# clogic.net
KiCad netlist of a schematic drawn in EAGLE
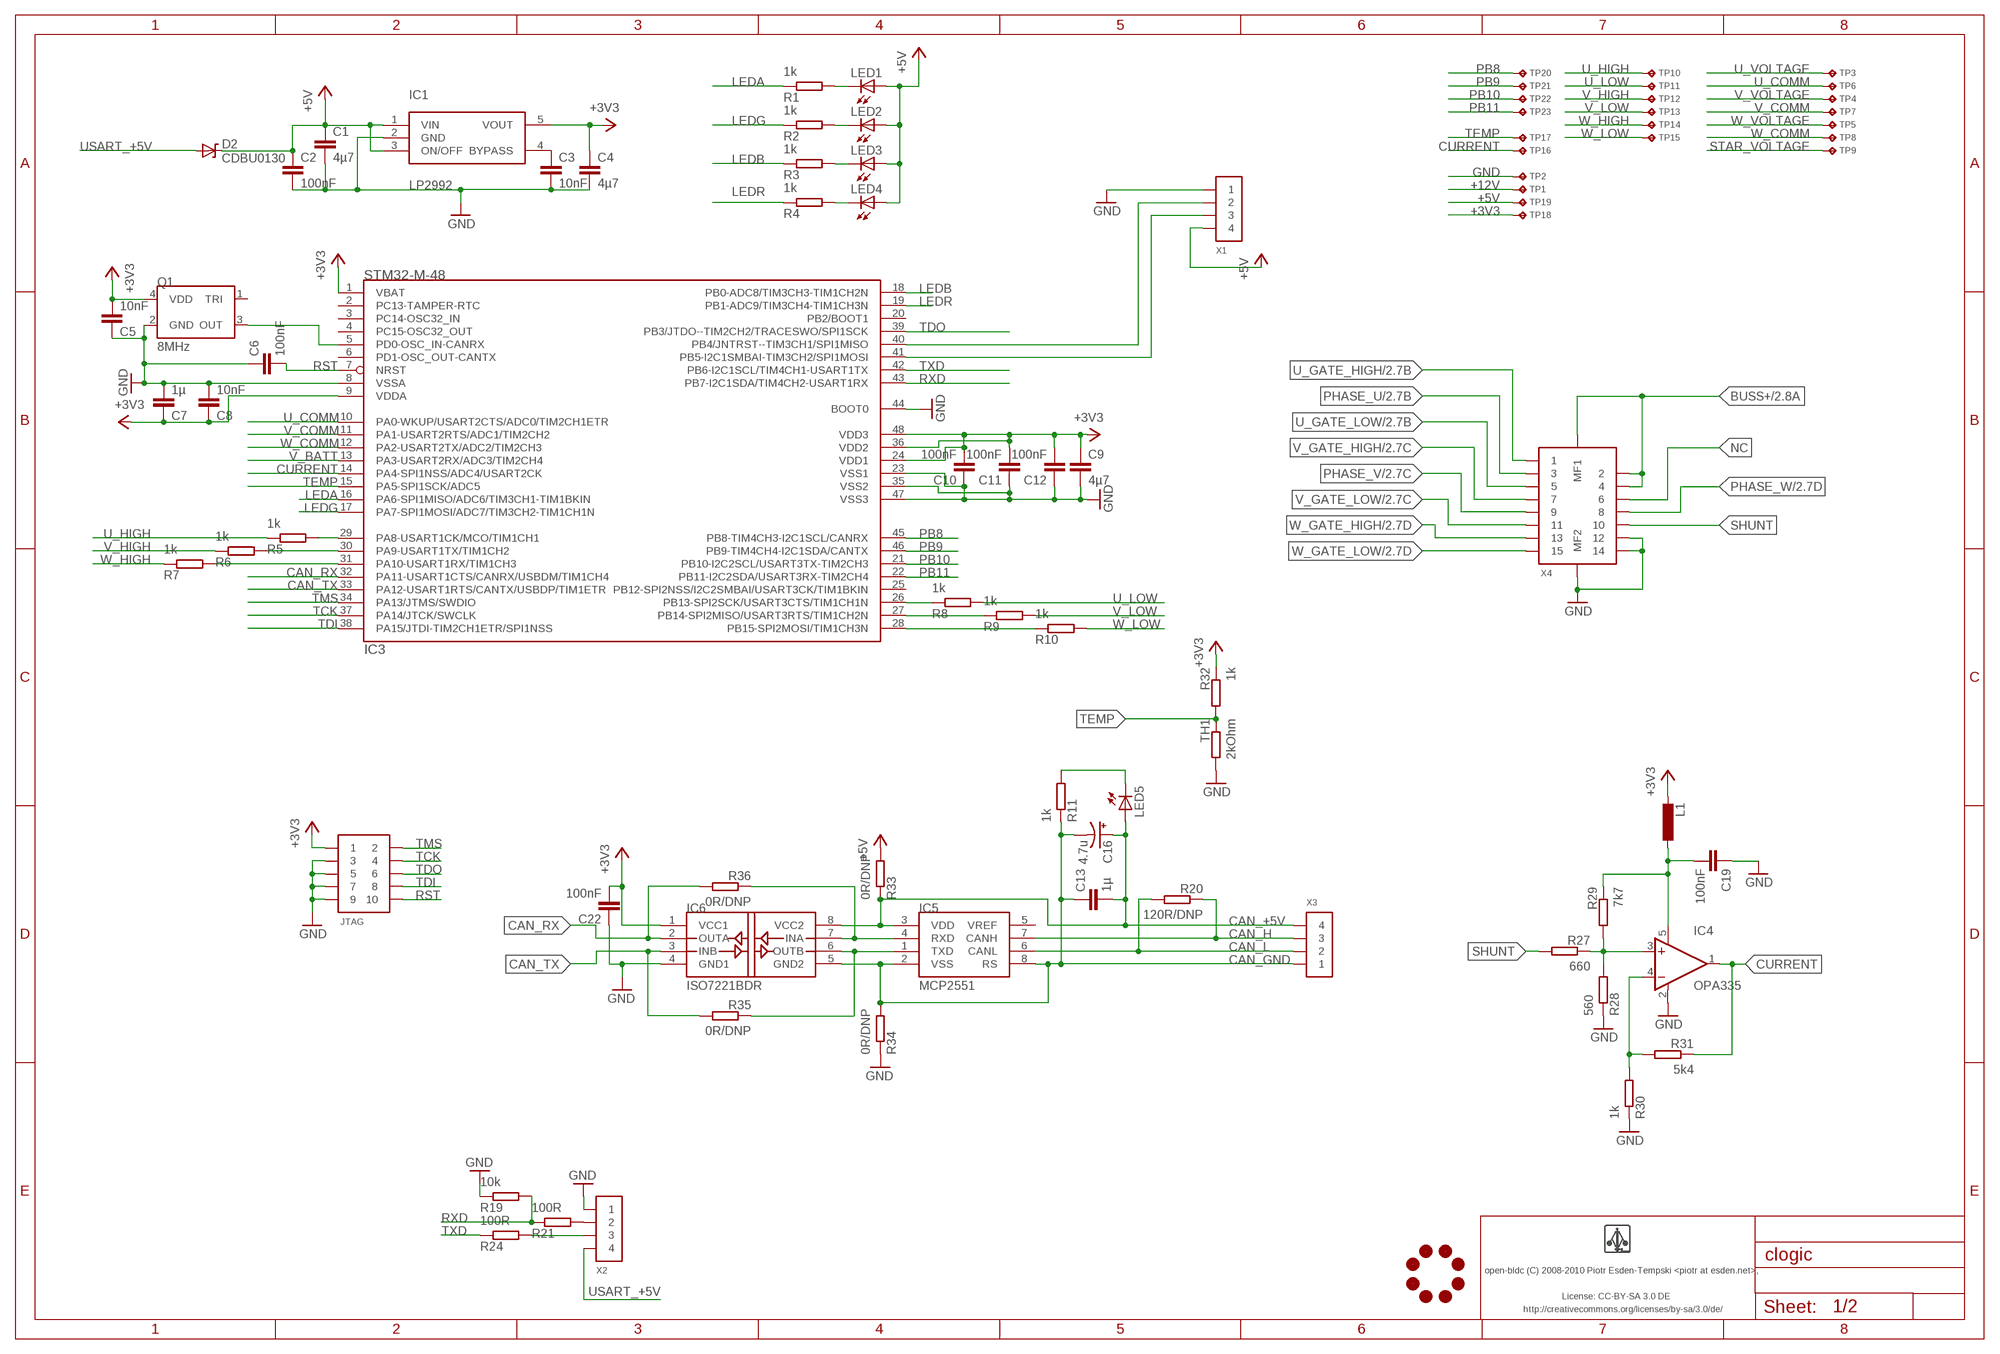
[diagram p0: schematic, sheet 1]
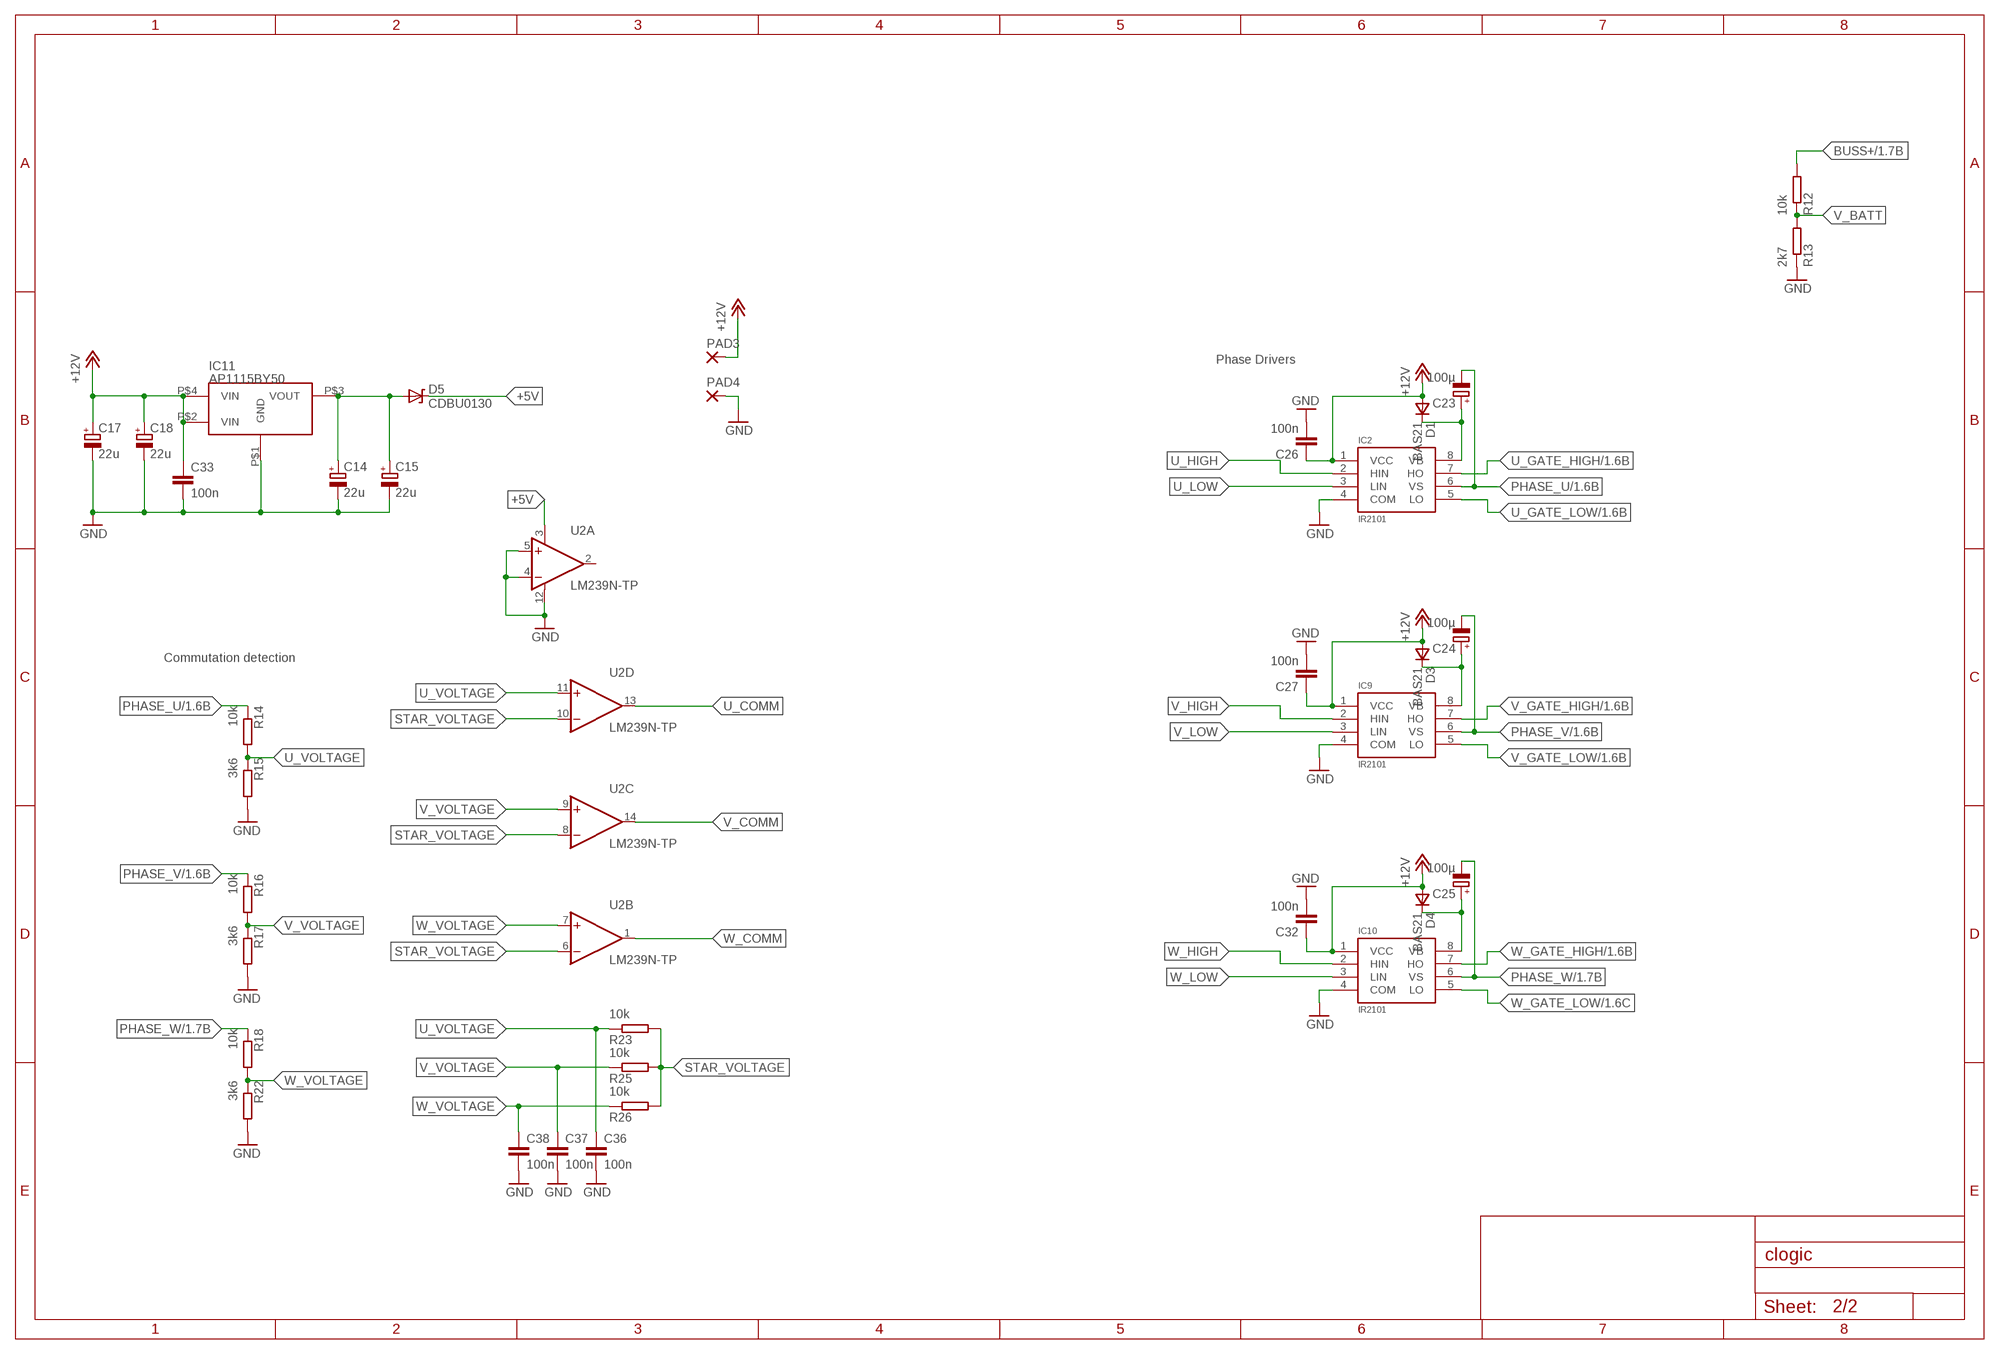
[diagram p1: schematic, sheet 2]

(export (version "E")
  (design (tool "Eeschema 10.0.6"))
  (components
    (comp (ref "C14")
      (value "22u")
      (footprint "eagle-import:0805-POL-CAP")
      (libsource (lib "eagle-import") (part "CAPACITOR-POL-0805"))
    )
    (comp (ref "C15")
      (value "22u")
      (footprint "eagle-import:0805-POL-CAP")
      (libsource (lib "eagle-import") (part "CAPACITOR-POL-0805"))
    )
    (comp (ref "C17")
      (value "22u")
      (footprint "eagle-import:0805-POL-CAP")
      (libsource (lib "eagle-import") (part "CAPACITOR-POL-0805"))
    )
    (comp (ref "C18")
      (value "22u")
      (footprint "eagle-import:0805-POL-CAP")
      (libsource (lib "eagle-import") (part "CAPACITOR-POL-0805"))
    )
    (comp (ref "C23")
      (value "100µ")
      (footprint "eagle-import:0805-POL-CAP")
      (libsource (lib "eagle-import") (part "CAPACITOR-POL-0805"))
    )
    (comp (ref "C24")
      (value "100µ")
      (footprint "eagle-import:0805-POL-CAP")
      (libsource (lib "eagle-import") (part "CAPACITOR-POL-0805"))
    )
    (comp (ref "C25")
      (value "100µ")
      (footprint "eagle-import:0805-POL-CAP")
      (libsource (lib "eagle-import") (part "CAPACITOR-POL-0805"))
    )
    (comp (ref "C26")
      (value "100n")
      (footprint "eagle-import:0603-CAP")
      (libsource (lib "eagle-import") (part "CAPACITOR-0603"))
    )
    (comp (ref "C27")
      (value "100n")
      (footprint "eagle-import:0603-CAP")
      (libsource (lib "eagle-import") (part "CAPACITOR-0603"))
    )
    (comp (ref "C32")
      (value "100n")
      (footprint "eagle-import:0603-CAP")
      (libsource (lib "eagle-import") (part "CAPACITOR-0603"))
    )
    (comp (ref "C33")
      (value "100n")
      (footprint "eagle-import:0603-CAP")
      (libsource (lib "eagle-import") (part "CAPACITOR-0603"))
    )
    (comp (ref "C36")
      (value "100n")
      (footprint "eagle-import:0603-CAP")
      (libsource (lib "eagle-import") (part "CAPACITOR-0603"))
    )
    (comp (ref "C37")
      (value "100n")
      (footprint "eagle-import:0603-CAP")
      (libsource (lib "eagle-import") (part "CAPACITOR-0603"))
    )
    (comp (ref "C38")
      (value "100n")
      (footprint "eagle-import:0603-CAP")
      (libsource (lib "eagle-import") (part "CAPACITOR-0603"))
    )
    (comp (ref "D1")
      (value "BAS21")
      (footprint "eagle-import:SOT-23")
      (libsource (lib "eagle-import") (part "VAR2SOT23"))
    )
    (comp (ref "D3")
      (value "BAS21")
      (footprint "eagle-import:SOT-23")
      (libsource (lib "eagle-import") (part "VAR2SOT23"))
    )
    (comp (ref "D4")
      (value "BAS21")
      (footprint "eagle-import:SOT-23")
      (libsource (lib "eagle-import") (part "VAR2SOT23"))
    )
    (comp (ref "D5")
      (value "CDBU0130")
      (footprint "eagle-import:0603-LED")
      (libsource (lib "eagle-import") (part "DIODE-ZENER-0603"))
    )
    (comp (ref "IC2")
      (value "IR2101")
      (footprint "eagle-import:SO-8")
      (libsource (lib "eagle-import") (part "IR2101"))
    )
    (comp (ref "IC9")
      (value "IR2101")
      (footprint "eagle-import:SO-8")
      (libsource (lib "eagle-import") (part "IR2101"))
    )
    (comp (ref "IC10")
      (value "IR2101")
      (footprint "eagle-import:SO-8")
      (libsource (lib "eagle-import") (part "IR2101"))
    )
    (comp (ref "IC11")
      (value "AP1115BY50")
      (footprint "eagle-import:SOT89")
      (libsource (lib "eagle-import") (part "AP1115BY50"))
    )
    (comp (ref "PAD3")
      (value "SMD5")
      (footprint "eagle-import:SMD2,54-5,08")
      (libsource (lib "eagle-import") (part "SMD5"))
    )
    (comp (ref "PAD4")
      (value "SMD5")
      (footprint "eagle-import:SMD2,54-5,08")
      (libsource (lib "eagle-import") (part "SMD5"))
    )
    (comp (ref "R12")
      (value "10k")
      (footprint "eagle-import:0603-RES")
      (libsource (lib "eagle-import") (part "RESISTOR-0603"))
    )
    (comp (ref "R13")
      (value "2k7")
      (footprint "eagle-import:0603-RES")
      (libsource (lib "eagle-import") (part "RESISTOR-0603"))
    )
    (comp (ref "R14")
      (value "10k")
      (footprint "eagle-import:0603-RES")
      (libsource (lib "eagle-import") (part "RESISTOR-0603"))
    )
    (comp (ref "R15")
      (value "3k6")
      (footprint "eagle-import:0603-RES")
      (libsource (lib "eagle-import") (part "RESISTOR-0603"))
    )
    (comp (ref "R16")
      (value "10k")
      (footprint "eagle-import:0603-RES")
      (libsource (lib "eagle-import") (part "RESISTOR-0603"))
    )
    (comp (ref "R17")
      (value "3k6")
      (footprint "eagle-import:0603-RES")
      (libsource (lib "eagle-import") (part "RESISTOR-0603"))
    )
    (comp (ref "R18")
      (value "10k")
      (footprint "eagle-import:0603-RES")
      (libsource (lib "eagle-import") (part "RESISTOR-0603"))
    )
    (comp (ref "R22")
      (value "3k6")
      (footprint "eagle-import:0603-RES")
      (libsource (lib "eagle-import") (part "RESISTOR-0603"))
    )
    (comp (ref "R23")
      (value "10k")
      (footprint "eagle-import:0603-RES")
      (libsource (lib "eagle-import") (part "RESISTOR-0603"))
    )
    (comp (ref "R25")
      (value "10k")
      (footprint "eagle-import:0603-RES")
      (libsource (lib "eagle-import") (part "RESISTOR-0603"))
    )
    (comp (ref "R26")
      (value "10k")
      (footprint "eagle-import:0603-RES")
      (libsource (lib "eagle-import") (part "RESISTOR-0603"))
    )
    (comp (ref "U2")
      (value "LM239N-TP")
      (footprint "eagle-import:TSSOP_14")
      (libsource (lib "eagle-import") (part "LM239N-TP"))
    )
    (comp (ref "C1")
      (value "4µ7")
      (footprint "eagle-import:0603-CAP")
      (libsource (lib "eagle-import") (part "CAPACITOR-0603"))
    )
    (comp (ref "C2")
      (value "100nF")
      (footprint "eagle-import:0603-CAP")
      (libsource (lib "eagle-import") (part "CAPACITOR-0603"))
    )
    (comp (ref "C3")
      (value "10nF")
      (footprint "eagle-import:0603-CAP")
      (libsource (lib "eagle-import") (part "CAPACITOR-0603"))
    )
    (comp (ref "C4")
      (value "4µ7")
      (footprint "eagle-import:0603-CAP")
      (libsource (lib "eagle-import") (part "CAPACITOR-0603"))
    )
    (comp (ref "C5")
      (value "10nF")
      (footprint "eagle-import:0603-CAP")
      (libsource (lib "eagle-import") (part "CAPACITOR-0603"))
    )
    (comp (ref "C6")
      (value "100nF")
      (footprint "eagle-import:0603-CAP")
      (libsource (lib "eagle-import") (part "CAPACITOR-0603"))
    )
    (comp (ref "C7")
      (value "1µ")
      (footprint "eagle-import:0603-CAP")
      (libsource (lib "eagle-import") (part "CAPACITOR-0603"))
    )
    (comp (ref "C8")
      (value "10nF")
      (footprint "eagle-import:0603-CAP")
      (libsource (lib "eagle-import") (part "CAPACITOR-0603"))
    )
    (comp (ref "C9")
      (value "4µ7")
      (footprint "eagle-import:0603-CAP")
      (libsource (lib "eagle-import") (part "CAPACITOR-0603"))
    )
    (comp (ref "C10")
      (value "100nF")
      (footprint "eagle-import:0603-CAP")
      (libsource (lib "eagle-import") (part "CAPACITOR-0603"))
    )
    (comp (ref "C11")
      (value "100nF")
      (footprint "eagle-import:0603-CAP")
      (libsource (lib "eagle-import") (part "CAPACITOR-0603"))
    )
    (comp (ref "C12")
      (value "100nF")
      (footprint "eagle-import:0603-CAP")
      (libsource (lib "eagle-import") (part "CAPACITOR-0603"))
    )
    (comp (ref "C13")
      (value "1µ")
      (footprint "eagle-import:0603-CAP")
      (libsource (lib "eagle-import") (part "CAPACITOR-0603"))
    )
    (comp (ref "C16")
      (value "4.7u")
      (footprint "eagle-import:CAP_0805TANT_F95")
      (libsource (lib "eagle-import") (part "CPOL-US"))
    )
    (comp (ref "C19")
      (value "100nF")
      (footprint "eagle-import:0603-CAP")
      (libsource (lib "eagle-import") (part "CAPACITOR-0603"))
    )
    (comp (ref "C22")
      (value "100nF")
      (footprint "eagle-import:0603-CAP")
      (libsource (lib "eagle-import") (part "CAPACITOR-0603"))
    )
    (comp (ref "D2")
      (value "CDBU0130")
      (footprint "eagle-import:0603-LED")
      (libsource (lib "eagle-import") (part "DIODE-ZENER-0603"))
    )
    (comp (ref "IC1")
      (value "LP2992")
      (footprint "eagle-import:SOT23-5")
      (libsource (lib "eagle-import") (part "LP2992"))
    )
    (comp (ref "IC3")
      (value "STM32-M-48")
      (footprint "eagle-import:LQFP48")
      (libsource (lib "eagle-import") (part "STM32-M-48"))
    )
    (comp (ref "IC4")
      (value "OPA335")
      (footprint "eagle-import:SOT23-5")
      (libsource (lib "eagle-import") (part "OPA335"))
    )
    (comp (ref "IC5")
      (value "MCP2551")
      (footprint "eagle-import:SO8")
      (libsource (lib "eagle-import") (part "MCP2551"))
    )
    (comp (ref "IC6")
      (value "ISO7221BDR")
      (footprint "eagle-import:SO8")
      (libsource (lib "eagle-import") (part "ISO7221"))
    )
    (comp (ref "JL1")
      (value "JOBY_LOGO-6MIL")
      (footprint "eagle-import:JOBY_LOGO_6MIL")
      (libsource (lib "eagle-import") (part "JOBY_LOGO-6MIL"))
    )
    (comp (ref "JTAG")
      (value "CONN_5-2-FTSH-V")
      (footprint "eagle-import:FTSH-105-DV")
      (libsource (lib "eagle-import") (part "CONN_5-2-FTSH-V"))
    )
    (comp (ref "L1")
      (value "INDUCTOR-0603")
      (footprint "eagle-import:0603-IND")
      (libsource (lib "eagle-import") (part "INDUCTOR-0603"))
    )
    (comp (ref "LED1")
      (value "AMBER")
      (footprint "eagle-import:0603-LED")
      (libsource (lib "eagle-import") (part "LED-0603"))
    )
    (comp (ref "LED2")
      (value "GREEN")
      (footprint "eagle-import:0603-LED")
      (libsource (lib "eagle-import") (part "LED-0603"))
    )
    (comp (ref "LED3")
      (value "BLUE")
      (footprint "eagle-import:0603-LED")
      (libsource (lib "eagle-import") (part "LED-0603"))
    )
    (comp (ref "LED4")
      (value "RED")
      (footprint "eagle-import:0603-LED")
      (libsource (lib "eagle-import") (part "LED-0603"))
    )
    (comp (ref "LED5")
      (value "WHITE")
      (footprint "eagle-import:0603-LED")
      (libsource (lib "eagle-import") (part "LED-0603"))
    )
    (comp (ref "Q1")
      (value "8MHz")
      (footprint "eagle-import:ASE_OSCILLATOR")
      (libsource (lib "eagle-import") (part "ASE_ASCILLATOR"))
    )
    (comp (ref "R1")
      (value "1k")
      (footprint "eagle-import:0603-RES")
      (libsource (lib "eagle-import") (part "RESISTOR-0603"))
    )
    (comp (ref "R2")
      (value "1k")
      (footprint "eagle-import:0603-RES")
      (libsource (lib "eagle-import") (part "RESISTOR-0603"))
    )
    (comp (ref "R3")
      (value "1k")
      (footprint "eagle-import:0603-RES")
      (libsource (lib "eagle-import") (part "RESISTOR-0603"))
    )
    (comp (ref "R4")
      (value "1k")
      (footprint "eagle-import:0603-RES")
      (libsource (lib "eagle-import") (part "RESISTOR-0603"))
    )
    (comp (ref "R5")
      (value "1k")
      (footprint "eagle-import:0603-RES")
      (libsource (lib "eagle-import") (part "RESISTOR-0603"))
    )
    (comp (ref "R6")
      (value "1k")
      (footprint "eagle-import:0603-RES")
      (libsource (lib "eagle-import") (part "RESISTOR-0603"))
    )
    (comp (ref "R7")
      (value "1k")
      (footprint "eagle-import:0603-RES")
      (libsource (lib "eagle-import") (part "RESISTOR-0603"))
    )
    (comp (ref "R8")
      (value "1k")
      (footprint "eagle-import:0603-RES")
      (libsource (lib "eagle-import") (part "RESISTOR-0603"))
    )
    (comp (ref "R9")
      (value "1k")
      (footprint "eagle-import:0603-RES")
      (libsource (lib "eagle-import") (part "RESISTOR-0603"))
    )
    (comp (ref "R10")
      (value "1k")
      (footprint "eagle-import:0603-RES")
      (libsource (lib "eagle-import") (part "RESISTOR-0603"))
    )
    (comp (ref "R11")
      (value "1k")
      (footprint "eagle-import:0603-RES")
      (libsource (lib "eagle-import") (part "RESISTOR-0603"))
    )
    (comp (ref "R19")
      (value "10k")
      (footprint "eagle-import:0603-RES")
      (libsource (lib "eagle-import") (part "RESISTOR-0603"))
    )
    (comp (ref "R20")
      (value "120R/DNP")
      (footprint "eagle-import:0603-RES")
      (libsource (lib "eagle-import") (part "RESISTOR-0603"))
    )
    (comp (ref "R21")
      (value "100R")
      (footprint "eagle-import:0603-RES")
      (libsource (lib "eagle-import") (part "RESISTOR-0603"))
    )
    (comp (ref "R24")
      (value "100R")
      (footprint "eagle-import:0603-RES")
      (libsource (lib "eagle-import") (part "RESISTOR-0603"))
    )
    (comp (ref "R27")
      (value "660")
      (footprint "eagle-import:0603-RES")
      (libsource (lib "eagle-import") (part "RESISTOR-0603"))
    )
    (comp (ref "R28")
      (value "560")
      (footprint "eagle-import:0603-RES")
      (libsource (lib "eagle-import") (part "RESISTOR-0603"))
    )
    (comp (ref "R29")
      (value "7k7")
      (footprint "eagle-import:0603-RES")
      (libsource (lib "eagle-import") (part "RESISTOR-0603"))
    )
    (comp (ref "R30")
      (value "1k")
      (footprint "eagle-import:0603-RES")
      (libsource (lib "eagle-import") (part "RESISTOR-0603"))
    )
    (comp (ref "R31")
      (value "5k4")
      (footprint "eagle-import:0603-RES")
      (libsource (lib "eagle-import") (part "RESISTOR-0603"))
    )
    (comp (ref "R32")
      (value "1k")
      (footprint "eagle-import:0603-RES")
      (libsource (lib "eagle-import") (part "RESISTOR-0603"))
    )
    (comp (ref "R33")
      (value "0R/DNP")
      (footprint "eagle-import:0603-RES")
      (libsource (lib "eagle-import") (part "RESISTOR-0603"))
    )
    (comp (ref "R34")
      (value "0R/DNP")
      (footprint "eagle-import:0603-RES")
      (libsource (lib "eagle-import") (part "RESISTOR-0603"))
    )
    (comp (ref "R35")
      (value "0R/DNP")
      (footprint "eagle-import:0603-RES")
      (libsource (lib "eagle-import") (part "RESISTOR-0603"))
    )
    (comp (ref "R36")
      (value "0R/DNP")
      (footprint "eagle-import:0603-RES")
      (libsource (lib "eagle-import") (part "RESISTOR-0603"))
    )
    (comp (ref "TH1")
      (value "2kOhm")
      (footprint "eagle-import:0603-RES")
      (libsource (lib "eagle-import") (part "RESISTOR-0603"))
    )
    (comp (ref "TP1")
      (value "TP-09RSMD")
      (footprint "eagle-import:TP09R")
      (libsource (lib "eagle-import") (part "TP-09RSMD"))
    )
    (comp (ref "TP2")
      (value "TP-09RSMD")
      (footprint "eagle-import:TP09R")
      (libsource (lib "eagle-import") (part "TP-09RSMD"))
    )
    (comp (ref "TP3")
      (value "TP-09RSMD")
      (footprint "eagle-import:TP09R")
      (libsource (lib "eagle-import") (part "TP-09RSMD"))
    )
    (comp (ref "TP4")
      (value "TP-09RSMD")
      (footprint "eagle-import:TP09R")
      (libsource (lib "eagle-import") (part "TP-09RSMD"))
    )
    (comp (ref "TP5")
      (value "TP-09RSMD")
      (footprint "eagle-import:TP09R")
      (libsource (lib "eagle-import") (part "TP-09RSMD"))
    )
    (comp (ref "TP6")
      (value "TP-09RSMD")
      (footprint "eagle-import:TP09R")
      (libsource (lib "eagle-import") (part "TP-09RSMD"))
    )
    (comp (ref "TP7")
      (value "TP-09RSMD")
      (footprint "eagle-import:TP09R")
      (libsource (lib "eagle-import") (part "TP-09RSMD"))
    )
    (comp (ref "TP8")
      (value "TP-09RSMD")
      (footprint "eagle-import:TP09R")
      (libsource (lib "eagle-import") (part "TP-09RSMD"))
    )
    (comp (ref "TP9")
      (value "TP-09RSMD")
      (footprint "eagle-import:TP09R")
      (libsource (lib "eagle-import") (part "TP-09RSMD"))
    )
    (comp (ref "TP10")
      (value "TP-09RSMD")
      (footprint "eagle-import:TP09R")
      (libsource (lib "eagle-import") (part "TP-09RSMD"))
    )
    (comp (ref "TP11")
      (value "TP-09RSMD")
      (footprint "eagle-import:TP09R")
      (libsource (lib "eagle-import") (part "TP-09RSMD"))
    )
    (comp (ref "TP12")
      (value "TP-09RSMD")
      (footprint "eagle-import:TP09R")
      (libsource (lib "eagle-import") (part "TP-09RSMD"))
    )
    (comp (ref "TP13")
      (value "TP-09RSMD")
      (footprint "eagle-import:TP09R")
      (libsource (lib "eagle-import") (part "TP-09RSMD"))
    )
    (comp (ref "TP14")
      (value "TP-09RSMD")
      (footprint "eagle-import:TP09R")
      (libsource (lib "eagle-import") (part "TP-09RSMD"))
    )
    (comp (ref "TP15")
      (value "TP-09RSMD")
      (footprint "eagle-import:TP09R")
      (libsource (lib "eagle-import") (part "TP-09RSMD"))
    )
    (comp (ref "TP16")
      (value "TP-09RSMD")
      (footprint "eagle-import:TP09R")
      (libsource (lib "eagle-import") (part "TP-09RSMD"))
    )
    (comp (ref "TP17")
      (value "TP-09RSMD")
      (footprint "eagle-import:TP09R")
      (libsource (lib "eagle-import") (part "TP-09RSMD"))
    )
    (comp (ref "TP18")
      (value "TP-09RSMD")
      (footprint "eagle-import:TP09R")
      (libsource (lib "eagle-import") (part "TP-09RSMD"))
    )
    (comp (ref "TP19")
      (value "TP-09RSMD")
      (footprint "eagle-import:TP09R")
      (libsource (lib "eagle-import") (part "TP-09RSMD"))
    )
    (comp (ref "TP20")
      (value "TP-09RSMD")
      (footprint "eagle-import:TP09R")
      (libsource (lib "eagle-import") (part "TP-09RSMD"))
    )
    (comp (ref "TP21")
      (value "TP-09RSMD")
      (footprint "eagle-import:TP09R")
      (libsource (lib "eagle-import") (part "TP-09RSMD"))
    )
    (comp (ref "TP22")
      (value "TP-09RSMD")
      (footprint "eagle-import:TP09R")
      (libsource (lib "eagle-import") (part "TP-09RSMD"))
    )
    (comp (ref "TP23")
      (value "TP-09RSMD")
      (footprint "eagle-import:TP09R")
      (libsource (lib "eagle-import") (part "TP-09RSMD"))
    )
    (comp (ref "U$1")
      (value "LOGO")
      (footprint "eagle-import:LOGO")
      (libsource (lib "eagle-import") (part "LOGO-NORM"))
    )
    (comp (ref "X1")
      (value "CONN_4-1-53261")
      (footprint "eagle-import:PB-53261-04")
      (libsource (lib "eagle-import") (part "CONN_4-1-53261"))
    )
    (comp (ref "X2")
      (value "CONN_4-1-53261")
      (footprint "eagle-import:PB-53261-04")
      (libsource (lib "eagle-import") (part "CONN_4-1-53261"))
    )
    (comp (ref "X3")
      (value "CONN_4-1-53261")
      (footprint "eagle-import:PB-53261-04")
      (libsource (lib "eagle-import") (part "CONN_4-1-53261"))
    )
    (comp (ref "X4")
      (value "CONN_15-2-2MT-DF9")
      (footprint "eagle-import:DF9-15")
      (libsource (lib "eagle-import") (part "CONN_15-2-2MT-DF9"))
    )
  )
  (nets
    (net (code "1") (name "+3V3") (class "Default")
      (node (ref "C10") (pin "P$2") (pinfunction "2_P$2") (pintype "passive"))
      (node (ref "C11") (pin "P$2") (pinfunction "2_P$2") (pintype "passive"))
      (node (ref "C12") (pin "P$2") (pinfunction "2_P$2") (pintype "passive"))
      (node (ref "C22") (pin "P$2") (pinfunction "2_P$2") (pintype "passive"))
      (node (ref "C4") (pin "P$1") (pinfunction "1_P$1") (pintype "passive"))
      (node (ref "C5") (pin "P$2") (pinfunction "2_P$2") (pintype "passive"))
      (node (ref "C7") (pin "P$1") (pinfunction "1_P$1") (pintype "passive"))
      (node (ref "C8") (pin "P$1") (pinfunction "1_P$1") (pintype "passive"))
      (node (ref "C9") (pin "P$1") (pinfunction "1_P$1") (pintype "passive"))
      (node (ref "IC1") (pin "5") (pinfunction "VOUT_5") (pintype "bidirectional"))
      (node (ref "IC3") (pin "1") (pinfunction "VBAT_1") (pintype "power_in"))
      (node (ref "IC3") (pin "24") (pinfunction "VDD1_24") (pintype "power_in"))
      (node (ref "IC3") (pin "36") (pinfunction "VDD2_36") (pintype "power_in"))
      (node (ref "IC3") (pin "48") (pinfunction "VDD3_48") (pintype "power_in"))
      (node (ref "IC3") (pin "9") (pinfunction "VDDA_9") (pintype "power_in"))
      (node (ref "IC6") (pin "1") (pinfunction "VCC1_1") (pintype "bidirectional"))
      (node (ref "JTAG") (pin "1") (pinfunction "1_1") (pintype "bidirectional"))
      (node (ref "L1") (pin "P$2") (pinfunction "2_P$2") (pintype "passive"))
      (node (ref "Q1") (pin "4") (pinfunction "VDD_4") (pintype "power_in"))
      (node (ref "R32") (pin "P$1") (pinfunction "1_P$1") (pintype "passive"))
      (node (ref "TP18") (pin "P$1") (pinfunction "1_P$1") (pintype "bidirectional"))
    )
    (net (code "2") (name "+5V") (class "Default")
      (node (ref "C1") (pin "P$1") (pinfunction "1_P$1") (pintype "passive"))
      (node (ref "C2") (pin "P$1") (pinfunction "1_P$1") (pintype "passive"))
      (node (ref "D2") (pin "C") (pinfunction "C_C") (pintype "passive"))
      (node (ref "D5") (pin "C") (pinfunction "C_C") (pintype "passive"))
      (node (ref "IC1") (pin "1") (pinfunction "VIN_1") (pintype "bidirectional"))
      (node (ref "IC1") (pin "3") (pinfunction "ON/OFF_3") (pintype "bidirectional"))
      (node (ref "LED1") (pin "A") (pinfunction "A_A") (pintype "passive"))
      (node (ref "LED2") (pin "A") (pinfunction "A_A") (pintype "passive"))
      (node (ref "LED3") (pin "A") (pinfunction "A_A") (pintype "passive"))
      (node (ref "LED4") (pin "A") (pinfunction "A_A") (pintype "passive"))
      (node (ref "R33") (pin "P$2") (pinfunction "2_P$2") (pintype "passive"))
      (node (ref "TP19") (pin "P$1") (pinfunction "1_P$1") (pintype "bidirectional"))
      (node (ref "U2") (pin "3") (pinfunction "V+_3") (pintype "power_in"))
      (node (ref "X1") (pin "4") (pinfunction "4_4") (pintype "bidirectional"))
    )
    (net (code "3") (name "+12V") (class "Default")
      (node (ref "C17") (pin "+") (pinfunction "+_+") (pintype "passive"))
      (node (ref "C18") (pin "+") (pinfunction "+_+") (pintype "passive"))
      (node (ref "C26") (pin "P$1") (pinfunction "1_P$1") (pintype "passive"))
      (node (ref "C27") (pin "P$1") (pinfunction "1_P$1") (pintype "passive"))
      (node (ref "C32") (pin "P$1") (pinfunction "1_P$1") (pintype "passive"))
      (node (ref "C33") (pin "P$1") (pinfunction "1_P$1") (pintype "passive"))
      (node (ref "D1") (pin "3") (pinfunction "A_3") (pintype "passive"))
      (node (ref "D3") (pin "3") (pinfunction "A_3") (pintype "passive"))
      (node (ref "D4") (pin "3") (pinfunction "A_3") (pintype "passive"))
      (node (ref "IC10") (pin "1") (pinfunction "VCC_1") (pintype "bidirectional"))
      (node (ref "IC11") (pin "P$2") (pinfunction "VIN_P$2") (pintype "power_in"))
      (node (ref "IC11") (pin "P$4") (pinfunction "VIN_P$4") (pintype "input"))
      (node (ref "IC2") (pin "1") (pinfunction "VCC_1") (pintype "bidirectional"))
      (node (ref "IC9") (pin "1") (pinfunction "VCC_1") (pintype "bidirectional"))
      (node (ref "PAD3") (pin "1") (pinfunction "P_1") (pintype "passive"))
      (node (ref "TP1") (pin "P$1") (pinfunction "1_P$1") (pintype "bidirectional"))
    )
    (net (code "4") (name "BUSS+") (class "Default")
      (node (ref "R12") (pin "P$2") (pinfunction "2_P$2") (pintype "passive"))
      (node (ref "X4") (pin "2") (pinfunction "2_2") (pintype "bidirectional"))
      (node (ref "X4") (pin "4") (pinfunction "4_4") (pintype "bidirectional"))
      (node (ref "X4") (pin "MF1") (pinfunction "MF1_MF1") (pintype "bidirectional"))
    )
    (net (code "5") (name "CAN_+5V") (class "Default")
      (node (ref "C13") (pin "P$2") (pinfunction "2_P$2") (pintype "passive"))
      (node (ref "C16") (pin "P$1") (pinfunction "+_P$1") (pintype "passive"))
      (node (ref "IC5") (pin "3") (pinfunction "VDD_3") (pintype "bidirectional"))
      (node (ref "IC6") (pin "8") (pinfunction "VCC2_8") (pintype "bidirectional"))
      (node (ref "LED5") (pin "A") (pinfunction "A_A") (pintype "passive"))
      (node (ref "R33") (pin "P$1") (pinfunction "1_P$1") (pintype "passive"))
      (node (ref "X3") (pin "4") (pinfunction "4_4") (pintype "bidirectional"))
    )
    (net (code "6") (name "CAN_GND") (class "Default")
      (node (ref "C13") (pin "P$1") (pinfunction "1_P$1") (pintype "passive"))
      (node (ref "C16") (pin "P$2") (pinfunction "-_P$2") (pintype "passive"))
      (node (ref "IC5") (pin "2") (pinfunction "VSS_2") (pintype "bidirectional"))
      (node (ref "IC5") (pin "8") (pinfunction "RS_8") (pintype "bidirectional"))
      (node (ref "IC6") (pin "5") (pinfunction "GND2_5") (pintype "bidirectional"))
      (node (ref "R11") (pin "P$1") (pinfunction "1_P$1") (pintype "passive"))
      (node (ref "R34") (pin "P$2") (pinfunction "2_P$2") (pintype "passive"))
      (node (ref "X3") (pin "1") (pinfunction "1_1") (pintype "bidirectional"))
    )
    (net (code "7") (name "CAN_H") (class "Default")
      (node (ref "IC5") (pin "7") (pinfunction "CANH_7") (pintype "bidirectional"))
      (node (ref "R20") (pin "P$1") (pinfunction "1_P$1") (pintype "passive"))
      (node (ref "X3") (pin "3") (pinfunction "3_3") (pintype "bidirectional"))
    )
    (net (code "8") (name "CAN_L") (class "Default")
      (node (ref "IC5") (pin "6") (pinfunction "CANL_6") (pintype "bidirectional"))
      (node (ref "R20") (pin "P$2") (pinfunction "2_P$2") (pintype "passive"))
      (node (ref "X3") (pin "2") (pinfunction "2_2") (pintype "bidirectional"))
    )
    (net (code "9") (name "CAN_RX") (class "Default")
      (node (ref "IC3") (pin "32") (pinfunction "PA11-USART1CTS/CANRX/USBDM/TIM1CH4_32") (pintype "bidirectional"))
      (node (ref "IC6") (pin "2") (pinfunction "OUTA_2") (pintype "bidirectional"))
      (node (ref "R36") (pin "P$2") (pinfunction "2_P$2") (pintype "passive"))
    )
    (net (code "10") (name "CAN_TX") (class "Default")
      (node (ref "IC3") (pin "33") (pinfunction "PA12-USART1RTS/CANTX/USBDP/TIM1ETR_33") (pintype "bidirectional"))
      (node (ref "IC6") (pin "3") (pinfunction "INB_3") (pintype "bidirectional"))
      (node (ref "R35") (pin "P$2") (pinfunction "2_P$2") (pintype "passive"))
    )
    (net (code "11") (name "CURRENT") (class "Default")
      (node (ref "IC3") (pin "14") (pinfunction "PA4-SPI1NSS/ADC4/USART2CK_14") (pintype "bidirectional"))
      (node (ref "IC4") (pin "1") (pinfunction "OUT_1") (pintype "output"))
      (node (ref "R31") (pin "P$1") (pinfunction "1_P$1") (pintype "passive"))
      (node (ref "TP16") (pin "P$1") (pinfunction "1_P$1") (pintype "bidirectional"))
    )
    (net (code "12") (name "GND") (class "Default")
      (node (ref "C1") (pin "P$2") (pinfunction "2_P$2") (pintype "passive"))
      (node (ref "C10") (pin "P$1") (pinfunction "1_P$1") (pintype "passive"))
      (node (ref "C11") (pin "P$1") (pinfunction "1_P$1") (pintype "passive"))
      (node (ref "C12") (pin "P$1") (pinfunction "1_P$1") (pintype "passive"))
      (node (ref "C14") (pin "-") (pinfunction "-_-") (pintype "passive"))
      (node (ref "C15") (pin "-") (pinfunction "-_-") (pintype "passive"))
      (node (ref "C17") (pin "-") (pinfunction "-_-") (pintype "passive"))
      (node (ref "C18") (pin "-") (pinfunction "-_-") (pintype "passive"))
      (node (ref "C19") (pin "P$1") (pinfunction "1_P$1") (pintype "passive"))
      (node (ref "C2") (pin "P$2") (pinfunction "2_P$2") (pintype "passive"))
      (node (ref "C22") (pin "P$1") (pinfunction "1_P$1") (pintype "passive"))
      (node (ref "C26") (pin "P$2") (pinfunction "2_P$2") (pintype "passive"))
      (node (ref "C27") (pin "P$2") (pinfunction "2_P$2") (pintype "passive"))
      (node (ref "C3") (pin "P$2") (pinfunction "2_P$2") (pintype "passive"))
      (node (ref "C32") (pin "P$2") (pinfunction "2_P$2") (pintype "passive"))
      (node (ref "C33") (pin "P$2") (pinfunction "2_P$2") (pintype "passive"))
      (node (ref "C36") (pin "P$2") (pinfunction "2_P$2") (pintype "passive"))
      (node (ref "C37") (pin "P$2") (pinfunction "2_P$2") (pintype "passive"))
      (node (ref "C38") (pin "P$2") (pinfunction "2_P$2") (pintype "passive"))
      (node (ref "C4") (pin "P$2") (pinfunction "2_P$2") (pintype "passive"))
      (node (ref "C5") (pin "P$1") (pinfunction "1_P$1") (pintype "passive"))
      (node (ref "C6") (pin "P$1") (pinfunction "1_P$1") (pintype "passive"))
      (node (ref "C7") (pin "P$2") (pinfunction "2_P$2") (pintype "passive"))
      (node (ref "C8") (pin "P$2") (pinfunction "2_P$2") (pintype "passive"))
      (node (ref "C9") (pin "P$2") (pinfunction "2_P$2") (pintype "passive"))
      (node (ref "IC1") (pin "2") (pinfunction "GND_2") (pintype "bidirectional"))
      (node (ref "IC10") (pin "4") (pinfunction "COM_4") (pintype "bidirectional"))
      (node (ref "IC11") (pin "P$1") (pinfunction "GND_P$1") (pintype "power_in"))
      (node (ref "IC2") (pin "4") (pinfunction "COM_4") (pintype "bidirectional"))
      (node (ref "IC3") (pin "23") (pinfunction "VSS1_23") (pintype "power_in"))
      (node (ref "IC3") (pin "35") (pinfunction "VSS2_35") (pintype "power_in"))
      (node (ref "IC3") (pin "44") (pinfunction "BOOT0_44") (pintype "input"))
      (node (ref "IC3") (pin "47") (pinfunction "VSS3_47") (pintype "power_in"))
      (node (ref "IC3") (pin "8") (pinfunction "VSSA_8") (pintype "power_in"))
      (node (ref "IC4") (pin "2") (pinfunction "V-_2") (pintype "power_in"))
      (node (ref "IC6") (pin "4") (pinfunction "GND1_4") (pintype "bidirectional"))
      (node (ref "IC9") (pin "4") (pinfunction "COM_4") (pintype "bidirectional"))
      (node (ref "JTAG") (pin "3") (pinfunction "3_3") (pintype "bidirectional"))
      (node (ref "JTAG") (pin "5") (pinfunction "5_5") (pintype "bidirectional"))
      (node (ref "JTAG") (pin "7") (pinfunction "7_7") (pintype "bidirectional"))
      (node (ref "JTAG") (pin "9") (pinfunction "9_9") (pintype "bidirectional"))
      (node (ref "PAD4") (pin "1") (pinfunction "P_1") (pintype "passive"))
      (node (ref "Q1") (pin "2") (pinfunction "GND_2") (pintype "power_in"))
      (node (ref "R13") (pin "P$1") (pinfunction "1_P$1") (pintype "passive"))
      (node (ref "R15") (pin "P$2") (pinfunction "2_P$2") (pintype "passive"))
      (node (ref "R17") (pin "P$2") (pinfunction "2_P$2") (pintype "passive"))
      (node (ref "R19") (pin "P$1") (pinfunction "1_P$1") (pintype "passive"))
      (node (ref "R22") (pin "P$2") (pinfunction "2_P$2") (pintype "passive"))
      (node (ref "R28") (pin "P$1") (pinfunction "1_P$1") (pintype "passive"))
      (node (ref "R30") (pin "P$1") (pinfunction "1_P$1") (pintype "passive"))
      (node (ref "R34") (pin "P$1") (pinfunction "1_P$1") (pintype "passive"))
      (node (ref "TH1") (pin "P$2") (pinfunction "2_P$2") (pintype "passive"))
      (node (ref "TP2") (pin "P$1") (pinfunction "1_P$1") (pintype "bidirectional"))
      (node (ref "U2") (pin "12") (pinfunction "V-_12") (pintype "power_in"))
      (node (ref "U2") (pin "4") (pinfunction "-IN_4") (pintype "input"))
      (node (ref "U2") (pin "5") (pinfunction "+IN_5") (pintype "input"))
      (node (ref "X1") (pin "1") (pinfunction "1_1") (pintype "bidirectional"))
      (node (ref "X2") (pin "1") (pinfunction "1_1") (pintype "bidirectional"))
      (node (ref "X4") (pin "12") (pinfunction "12_12") (pintype "bidirectional"))
      (node (ref "X4") (pin "14") (pinfunction "14_14") (pintype "bidirectional"))
      (node (ref "X4") (pin "MF2") (pinfunction "MF2_MF2") (pintype "bidirectional"))
    )
    (net (code "13") (name "LEDA") (class "Default")
      (node (ref "IC3") (pin "16") (pinfunction "PA6-SPI1MISO/ADC6/TIM3CH1-TIM1BKIN_16") (pintype "bidirectional"))
      (node (ref "R1") (pin "P$1") (pinfunction "1_P$1") (pintype "passive"))
    )
    (net (code "14") (name "LEDB") (class "Default")
      (node (ref "IC3") (pin "18") (pinfunction "PB0-ADC8/TIM3CH3-TIM1CH2N_18") (pintype "bidirectional"))
      (node (ref "R3") (pin "P$1") (pinfunction "1_P$1") (pintype "passive"))
    )
    (net (code "15") (name "LEDG") (class "Default")
      (node (ref "IC3") (pin "17") (pinfunction "PA7-SPI1MOSI/ADC7/TIM3CH2-TIM1CH1N_17") (pintype "bidirectional"))
      (node (ref "R2") (pin "P$1") (pinfunction "1_P$1") (pintype "passive"))
    )
    (net (code "16") (name "LEDR") (class "Default")
      (node (ref "IC3") (pin "19") (pinfunction "PB1-ADC9/TIM3CH4-TIM1CH3N_19") (pintype "bidirectional"))
      (node (ref "R4") (pin "P$1") (pinfunction "1_P$1") (pintype "passive"))
    )
    (net (code "17") (name "NC") (class "Default")
      (node (ref "X4") (pin "6") (pinfunction "6_6") (pintype "bidirectional"))
    )
    (net (code "18") (name "Net-(C3-1)") (class "Default")
      (node (ref "C3") (pin "P$1") (pinfunction "1_P$1") (pintype "passive"))
      (node (ref "IC1") (pin "4") (pinfunction "BYPASS_4") (pintype "bidirectional"))
    )
    (net (code "19") (name "Net-(C19-2)") (class "Default")
      (node (ref "C19") (pin "P$2") (pinfunction "2_P$2") (pintype "passive"))
      (node (ref "IC4") (pin "5") (pinfunction "V+_5") (pintype "power_in"))
      (node (ref "L1") (pin "P$1") (pinfunction "1_P$1") (pintype "passive"))
      (node (ref "R29") (pin "P$1") (pinfunction "1_P$1") (pintype "passive"))
    )
    (net (code "20") (name "Net-(D1-C)") (class "Default")
      (node (ref "C23") (pin "+") (pinfunction "+_+") (pintype "passive"))
      (node (ref "D1") (pin "1") (pinfunction "C_1") (pintype "passive"))
      (node (ref "IC2") (pin "8") (pinfunction "VB_8") (pintype "bidirectional"))
    )
    (net (code "21") (name "Net-(D3-C)") (class "Default")
      (node (ref "C24") (pin "+") (pinfunction "+_+") (pintype "passive"))
      (node (ref "D3") (pin "1") (pinfunction "C_1") (pintype "passive"))
      (node (ref "IC9") (pin "8") (pinfunction "VB_8") (pintype "bidirectional"))
    )
    (net (code "22") (name "Net-(D4-C)") (class "Default")
      (node (ref "C25") (pin "+") (pinfunction "+_+") (pintype "passive"))
      (node (ref "D4") (pin "1") (pinfunction "C_1") (pintype "passive"))
      (node (ref "IC10") (pin "8") (pinfunction "VB_8") (pintype "bidirectional"))
    )
    (net (code "23") (name "Net-(IC3-PA8-USART1CK{slash}MCO{slash}TIM1CH1)") (class "Default")
      (node (ref "IC3") (pin "29") (pinfunction "PA8-USART1CK/MCO/TIM1CH1_29") (pintype "bidirectional"))
      (node (ref "R5") (pin "P$2") (pinfunction "2_P$2") (pintype "passive"))
    )
    (net (code "24") (name "Net-(IC3-PA9-USART1TX{slash}TIM1CH2)") (class "Default")
      (node (ref "IC3") (pin "30") (pinfunction "PA9-USART1TX/TIM1CH2_30") (pintype "bidirectional"))
      (node (ref "R6") (pin "P$2") (pinfunction "2_P$2") (pintype "passive"))
    )
    (net (code "25") (name "Net-(IC3-PA10-USART1RX{slash}TIM1CH3)") (class "Default")
      (node (ref "IC3") (pin "31") (pinfunction "PA10-USART1RX/TIM1CH3_31") (pintype "bidirectional"))
      (node (ref "R7") (pin "P$2") (pinfunction "2_P$2") (pintype "passive"))
    )
    (net (code "26") (name "Net-(IC3-PB4{slash}JNTRST--TIM3CH1{slash}SPI1MISO)") (class "Default")
      (node (ref "IC3") (pin "40") (pinfunction "PB4/JNTRST--TIM3CH1/SPI1MISO_40") (pintype "bidirectional"))
      (node (ref "X1") (pin "2") (pinfunction "2_2") (pintype "bidirectional"))
    )
    (net (code "27") (name "Net-(IC3-PB5-I2C1SMBAI-TIM3CH2{slash}SPI1MOSI)") (class "Default")
      (node (ref "IC3") (pin "41") (pinfunction "PB5-I2C1SMBAI-TIM3CH2/SPI1MOSI_41") (pintype "bidirectional"))
      (node (ref "X1") (pin "3") (pinfunction "3_3") (pintype "bidirectional"))
    )
    (net (code "28") (name "Net-(IC3-PB13-SPI2SCK{slash}USART3CTS{slash}TIM1CH1N)") (class "Default")
      (node (ref "IC3") (pin "26") (pinfunction "PB13-SPI2SCK/USART3CTS/TIM1CH1N_26") (pintype "bidirectional"))
      (node (ref "R8") (pin "P$1") (pinfunction "1_P$1") (pintype "passive"))
    )
    (net (code "29") (name "Net-(IC3-PB14-SPI2MISO{slash}USART3RTS{slash}TIM1CH2N)") (class "Default")
      (node (ref "IC3") (pin "27") (pinfunction "PB14-SPI2MISO/USART3RTS/TIM1CH2N_27") (pintype "bidirectional"))
      (node (ref "R9") (pin "P$1") (pinfunction "1_P$1") (pintype "passive"))
    )
    (net (code "30") (name "Net-(IC3-PB15-SPI2MOSI{slash}TIM1CH3N)") (class "Default")
      (node (ref "IC3") (pin "28") (pinfunction "PB15-SPI2MOSI/TIM1CH3N_28") (pintype "bidirectional"))
      (node (ref "R10") (pin "P$1") (pinfunction "1_P$1") (pintype "passive"))
    )
    (net (code "31") (name "Net-(IC3-PD0-OSC_IN-CANRX)") (class "Default")
      (node (ref "IC3") (pin "5") (pinfunction "PD0-OSC_IN-CANRX_5") (pintype "input"))
      (node (ref "Q1") (pin "3") (pinfunction "OUT_3") (pintype "output"))
    )
    (net (code "32") (name "Net-(IC4-+IN)") (class "Default")
      (node (ref "IC4") (pin "3") (pinfunction "+IN_3") (pintype "input"))
      (node (ref "R27") (pin "P$1") (pinfunction "1_P$1") (pintype "passive"))
      (node (ref "R28") (pin "P$2") (pinfunction "2_P$2") (pintype "passive"))
      (node (ref "R29") (pin "P$2") (pinfunction "2_P$2") (pintype "passive"))
    )
    (net (code "33") (name "Net-(IC4--IN)") (class "Default")
      (node (ref "IC4") (pin "4") (pinfunction "-IN_4") (pintype "input"))
      (node (ref "R30") (pin "P$2") (pinfunction "2_P$2") (pintype "passive"))
      (node (ref "R31") (pin "P$2") (pinfunction "2_P$2") (pintype "passive"))
    )
    (net (code "34") (name "Net-(IC5-RXD)") (class "Default")
      (node (ref "IC5") (pin "4") (pinfunction "RXD_4") (pintype "bidirectional"))
      (node (ref "IC6") (pin "7") (pinfunction "INA_7") (pintype "bidirectional"))
      (node (ref "R36") (pin "P$1") (pinfunction "1_P$1") (pintype "passive"))
    )
    (net (code "35") (name "Net-(IC5-TXD)") (class "Default")
      (node (ref "IC5") (pin "1") (pinfunction "TXD_1") (pintype "bidirectional"))
      (node (ref "IC6") (pin "6") (pinfunction "OUTB_6") (pintype "bidirectional"))
      (node (ref "R35") (pin "P$1") (pinfunction "1_P$1") (pintype "passive"))
    )
    (net (code "36") (name "Net-(IC11-VOUT)") (class "Default")
      (node (ref "C14") (pin "+") (pinfunction "+_+") (pintype "passive"))
      (node (ref "C15") (pin "+") (pinfunction "+_+") (pintype "passive"))
      (node (ref "D5") (pin "A") (pinfunction "A_A") (pintype "passive"))
      (node (ref "IC11") (pin "P$3") (pinfunction "VOUT_P$3") (pintype "power_in"))
    )
    (net (code "37") (name "Net-(R1-2)") (class "Default")
      (node (ref "LED1") (pin "C") (pinfunction "C_C") (pintype "passive"))
      (node (ref "R1") (pin "P$2") (pinfunction "2_P$2") (pintype "passive"))
    )
    (net (code "38") (name "Net-(R2-2)") (class "Default")
      (node (ref "LED2") (pin "C") (pinfunction "C_C") (pintype "passive"))
      (node (ref "R2") (pin "P$2") (pinfunction "2_P$2") (pintype "passive"))
    )
    (net (code "39") (name "Net-(R3-2)") (class "Default")
      (node (ref "LED3") (pin "C") (pinfunction "C_C") (pintype "passive"))
      (node (ref "R3") (pin "P$2") (pinfunction "2_P$2") (pintype "passive"))
    )
    (net (code "40") (name "Net-(R4-2)") (class "Default")
      (node (ref "LED4") (pin "C") (pinfunction "C_C") (pintype "passive"))
      (node (ref "R4") (pin "P$2") (pinfunction "2_P$2") (pintype "passive"))
    )
    (net (code "41") (name "Net-(R11-2)") (class "Default")
      (node (ref "LED5") (pin "C") (pinfunction "C_C") (pintype "passive"))
      (node (ref "R11") (pin "P$2") (pinfunction "2_P$2") (pintype "passive"))
    )
    (net (code "42") (name "Net-(R21-2)") (class "Default")
      (node (ref "R21") (pin "P$2") (pinfunction "2_P$2") (pintype "passive"))
      (node (ref "X2") (pin "2") (pinfunction "2_2") (pintype "bidirectional"))
    )
    (net (code "43") (name "Net-(R24-2)") (class "Default")
      (node (ref "R24") (pin "P$2") (pinfunction "2_P$2") (pintype "passive"))
      (node (ref "X2") (pin "3") (pinfunction "3_3") (pintype "bidirectional"))
    )
    (net (code "44") (name "PB8") (class "Default")
      (node (ref "IC3") (pin "45") (pinfunction "PB8-TIM4CH3-I2C1SCL/CANRX_45") (pintype "bidirectional"))
      (node (ref "TP20") (pin "P$1") (pinfunction "1_P$1") (pintype "bidirectional"))
    )
    (net (code "45") (name "PB9") (class "Default")
      (node (ref "IC3") (pin "46") (pinfunction "PB9-TIM4CH4-I2C1SDA/CANTX_46") (pintype "bidirectional"))
      (node (ref "TP21") (pin "P$1") (pinfunction "1_P$1") (pintype "bidirectional"))
    )
    (net (code "46") (name "PB10") (class "Default")
      (node (ref "IC3") (pin "21") (pinfunction "PB10-I2C2SCL/USART3TX-TIM2CH3_21") (pintype "bidirectional"))
      (node (ref "TP22") (pin "P$1") (pinfunction "1_P$1") (pintype "bidirectional"))
    )
    (net (code "47") (name "PB11") (class "Default")
      (node (ref "IC3") (pin "22") (pinfunction "PB11-I2C2SDA/USART3RX-TIM2CH4_22") (pintype "bidirectional"))
      (node (ref "TP23") (pin "P$1") (pinfunction "1_P$1") (pintype "bidirectional"))
    )
    (net (code "48") (name "PHASE_U") (class "Default")
      (node (ref "C23") (pin "-") (pinfunction "-_-") (pintype "passive"))
      (node (ref "IC2") (pin "6") (pinfunction "VS_6") (pintype "bidirectional"))
      (node (ref "R14") (pin "P$1") (pinfunction "1_P$1") (pintype "passive"))
      (node (ref "X4") (pin "3") (pinfunction "3_3") (pintype "bidirectional"))
    )
    (net (code "49") (name "PHASE_V") (class "Default")
      (node (ref "C24") (pin "-") (pinfunction "-_-") (pintype "passive"))
      (node (ref "IC9") (pin "6") (pinfunction "VS_6") (pintype "bidirectional"))
      (node (ref "R16") (pin "P$1") (pinfunction "1_P$1") (pintype "passive"))
      (node (ref "X4") (pin "9") (pinfunction "9_9") (pintype "bidirectional"))
    )
    (net (code "50") (name "PHASE_W") (class "Default")
      (node (ref "C25") (pin "-") (pinfunction "-_-") (pintype "passive"))
      (node (ref "IC10") (pin "6") (pinfunction "VS_6") (pintype "bidirectional"))
      (node (ref "R18") (pin "P$1") (pinfunction "1_P$1") (pintype "passive"))
      (node (ref "X4") (pin "8") (pinfunction "8_8") (pintype "bidirectional"))
    )
    (net (code "51") (name "RST") (class "Default")
      (node (ref "C6") (pin "P$2") (pinfunction "2_P$2") (pintype "passive"))
      (node (ref "IC3") (pin "7") (pinfunction "NRST_7") (pintype "bidirectional"))
      (node (ref "JTAG") (pin "10") (pinfunction "10_10") (pintype "bidirectional"))
    )
    (net (code "52") (name "RXD") (class "Default")
      (node (ref "IC3") (pin "43") (pinfunction "PB7-I2C1SDA/TIM4CH2-USART1RX_43") (pintype "bidirectional"))
      (node (ref "R19") (pin "P$2") (pinfunction "2_P$2") (pintype "passive"))
      (node (ref "R21") (pin "P$1") (pinfunction "1_P$1") (pintype "passive"))
    )
    (net (code "53") (name "SHUNT") (class "Default")
      (node (ref "R27") (pin "P$2") (pinfunction "2_P$2") (pintype "passive"))
      (node (ref "X4") (pin "10") (pinfunction "10_10") (pintype "bidirectional"))
    )
    (net (code "54") (name "STAR_VOLTAGE") (class "Default")
      (node (ref "R23") (pin "P$2") (pinfunction "2_P$2") (pintype "passive"))
      (node (ref "R25") (pin "P$2") (pinfunction "2_P$2") (pintype "passive"))
      (node (ref "R26") (pin "P$2") (pinfunction "2_P$2") (pintype "passive"))
      (node (ref "TP9") (pin "P$1") (pinfunction "1_P$1") (pintype "bidirectional"))
      (node (ref "U2") (pin "10") (pinfunction "-IN_10") (pintype "input"))
      (node (ref "U2") (pin "6") (pinfunction "-IN_6") (pintype "input"))
      (node (ref "U2") (pin "8") (pinfunction "-IN_8") (pintype "input"))
    )
    (net (code "55") (name "TCK") (class "Default")
      (node (ref "IC3") (pin "37") (pinfunction "PA14/JTCK/SWCLK_37") (pintype "bidirectional"))
      (node (ref "JTAG") (pin "4") (pinfunction "4_4") (pintype "bidirectional"))
    )
    (net (code "56") (name "TDI") (class "Default")
      (node (ref "IC3") (pin "38") (pinfunction "PA15/JTDI-TIM2CH1ETR/SPI1NSS_38") (pintype "bidirectional"))
      (node (ref "JTAG") (pin "8") (pinfunction "8_8") (pintype "bidirectional"))
    )
    (net (code "57") (name "TDO") (class "Default")
      (node (ref "IC3") (pin "39") (pinfunction "PB3/JTDO--TIM2CH2/TRACESWO/SPI1SCK_39") (pintype "bidirectional"))
      (node (ref "JTAG") (pin "6") (pinfunction "6_6") (pintype "bidirectional"))
    )
    (net (code "58") (name "TEMP") (class "Default")
      (node (ref "IC3") (pin "15") (pinfunction "PA5-SPI1SCK/ADC5_15") (pintype "bidirectional"))
      (node (ref "R32") (pin "P$2") (pinfunction "2_P$2") (pintype "passive"))
      (node (ref "TH1") (pin "P$1") (pinfunction "1_P$1") (pintype "passive"))
      (node (ref "TP17") (pin "P$1") (pinfunction "1_P$1") (pintype "bidirectional"))
    )
    (net (code "59") (name "TMS") (class "Default")
      (node (ref "IC3") (pin "34") (pinfunction "PA13/JTMS/SWDIO_34") (pintype "bidirectional"))
      (node (ref "JTAG") (pin "2") (pinfunction "2_2") (pintype "bidirectional"))
    )
    (net (code "60") (name "TXD") (class "Default")
      (node (ref "IC3") (pin "42") (pinfunction "PB6-I2C1SCL/TIM4CH1-USART1TX_42") (pintype "bidirectional"))
      (node (ref "R24") (pin "P$1") (pinfunction "1_P$1") (pintype "passive"))
    )
    (net (code "61") (name "USART_+5V") (class "Default")
      (node (ref "D2") (pin "A") (pinfunction "A_A") (pintype "passive"))
      (node (ref "X2") (pin "4") (pinfunction "4_4") (pintype "bidirectional"))
    )
    (net (code "62") (name "U_COMM") (class "Default")
      (node (ref "IC3") (pin "10") (pinfunction "PA0-WKUP/USART2CTS/ADC0/TIM2CH1ETR_10") (pintype "bidirectional"))
      (node (ref "TP6") (pin "P$1") (pinfunction "1_P$1") (pintype "bidirectional"))
      (node (ref "U2") (pin "13") (pinfunction "OUT_13") (pintype "output"))
    )
    (net (code "63") (name "U_GATE_HIGH") (class "Default")
      (node (ref "IC2") (pin "7") (pinfunction "HO_7") (pintype "bidirectional"))
      (node (ref "X4") (pin "1") (pinfunction "1_1") (pintype "bidirectional"))
    )
    (net (code "64") (name "U_GATE_LOW") (class "Default")
      (node (ref "IC2") (pin "5") (pinfunction "LO_5") (pintype "bidirectional"))
      (node (ref "X4") (pin "5") (pinfunction "5_5") (pintype "bidirectional"))
    )
    (net (code "65") (name "U_HIGH") (class "Default")
      (node (ref "IC2") (pin "2") (pinfunction "HIN_2") (pintype "bidirectional"))
      (node (ref "R5") (pin "P$1") (pinfunction "1_P$1") (pintype "passive"))
      (node (ref "TP10") (pin "P$1") (pinfunction "1_P$1") (pintype "bidirectional"))
    )
    (net (code "66") (name "U_LOW") (class "Default")
      (node (ref "IC2") (pin "3") (pinfunction "LIN_3") (pintype "bidirectional"))
      (node (ref "R8") (pin "P$2") (pinfunction "2_P$2") (pintype "passive"))
      (node (ref "TP11") (pin "P$1") (pinfunction "1_P$1") (pintype "bidirectional"))
    )
    (net (code "67") (name "U_VOLTAGE") (class "Default")
      (node (ref "C36") (pin "P$1") (pinfunction "1_P$1") (pintype "passive"))
      (node (ref "R14") (pin "P$2") (pinfunction "2_P$2") (pintype "passive"))
      (node (ref "R15") (pin "P$1") (pinfunction "1_P$1") (pintype "passive"))
      (node (ref "R23") (pin "P$1") (pinfunction "1_P$1") (pintype "passive"))
      (node (ref "TP3") (pin "P$1") (pinfunction "1_P$1") (pintype "bidirectional"))
      (node (ref "U2") (pin "11") (pinfunction "+IN_11") (pintype "input"))
    )
    (net (code "68") (name "V_BATT") (class "Default")
      (node (ref "IC3") (pin "13") (pinfunction "PA3-USART2RX/ADC3/TIM2CH4_13") (pintype "bidirectional"))
      (node (ref "R12") (pin "P$1") (pinfunction "1_P$1") (pintype "passive"))
      (node (ref "R13") (pin "P$2") (pinfunction "2_P$2") (pintype "passive"))
    )
    (net (code "69") (name "V_COMM") (class "Default")
      (node (ref "IC3") (pin "11") (pinfunction "PA1-USART2RTS/ADC1/TIM2CH2_11") (pintype "bidirectional"))
      (node (ref "TP7") (pin "P$1") (pinfunction "1_P$1") (pintype "bidirectional"))
      (node (ref "U2") (pin "14") (pinfunction "OUT_14") (pintype "output"))
    )
    (net (code "70") (name "V_GATE_HIGH") (class "Default")
      (node (ref "IC9") (pin "7") (pinfunction "HO_7") (pintype "bidirectional"))
      (node (ref "X4") (pin "7") (pinfunction "7_7") (pintype "bidirectional"))
    )
    (net (code "71") (name "V_GATE_LOW") (class "Default")
      (node (ref "IC9") (pin "5") (pinfunction "LO_5") (pintype "bidirectional"))
      (node (ref "X4") (pin "11") (pinfunction "11_11") (pintype "bidirectional"))
    )
    (net (code "72") (name "V_HIGH") (class "Default")
      (node (ref "IC9") (pin "2") (pinfunction "HIN_2") (pintype "bidirectional"))
      (node (ref "R6") (pin "P$1") (pinfunction "1_P$1") (pintype "passive"))
      (node (ref "TP12") (pin "P$1") (pinfunction "1_P$1") (pintype "bidirectional"))
    )
    (net (code "73") (name "V_LOW") (class "Default")
      (node (ref "IC9") (pin "3") (pinfunction "LIN_3") (pintype "bidirectional"))
      (node (ref "R9") (pin "P$2") (pinfunction "2_P$2") (pintype "passive"))
      (node (ref "TP13") (pin "P$1") (pinfunction "1_P$1") (pintype "bidirectional"))
    )
    (net (code "74") (name "V_VOLTAGE") (class "Default")
      (node (ref "C37") (pin "P$1") (pinfunction "1_P$1") (pintype "passive"))
      (node (ref "R16") (pin "P$2") (pinfunction "2_P$2") (pintype "passive"))
      (node (ref "R17") (pin "P$1") (pinfunction "1_P$1") (pintype "passive"))
      (node (ref "R25") (pin "P$1") (pinfunction "1_P$1") (pintype "passive"))
      (node (ref "TP4") (pin "P$1") (pinfunction "1_P$1") (pintype "bidirectional"))
      (node (ref "U2") (pin "9") (pinfunction "+IN_9") (pintype "input"))
    )
    (net (code "75") (name "W_COMM") (class "Default")
      (node (ref "IC3") (pin "12") (pinfunction "PA2-USART2TX/ADC2/TIM2CH3_12") (pintype "bidirectional"))
      (node (ref "TP8") (pin "P$1") (pinfunction "1_P$1") (pintype "bidirectional"))
      (node (ref "U2") (pin "1") (pinfunction "OUT_1") (pintype "output"))
    )
    (net (code "76") (name "W_GATE_HIGH") (class "Default")
      (node (ref "IC10") (pin "7") (pinfunction "HO_7") (pintype "bidirectional"))
      (node (ref "X4") (pin "13") (pinfunction "13_13") (pintype "bidirectional"))
    )
    (net (code "77") (name "W_GATE_LOW") (class "Default")
      (node (ref "IC10") (pin "5") (pinfunction "LO_5") (pintype "bidirectional"))
      (node (ref "X4") (pin "15") (pinfunction "15_15") (pintype "bidirectional"))
    )
    (net (code "78") (name "W_HIGH") (class "Default")
      (node (ref "IC10") (pin "2") (pinfunction "HIN_2") (pintype "bidirectional"))
      (node (ref "R7") (pin "P$1") (pinfunction "1_P$1") (pintype "passive"))
      (node (ref "TP14") (pin "P$1") (pinfunction "1_P$1") (pintype "bidirectional"))
    )
    (net (code "79") (name "W_LOW") (class "Default")
      (node (ref "IC10") (pin "3") (pinfunction "LIN_3") (pintype "bidirectional"))
      (node (ref "R10") (pin "P$2") (pinfunction "2_P$2") (pintype "passive"))
      (node (ref "TP15") (pin "P$1") (pinfunction "1_P$1") (pintype "bidirectional"))
    )
    (net (code "80") (name "W_VOLTAGE") (class "Default")
      (node (ref "C38") (pin "P$1") (pinfunction "1_P$1") (pintype "passive"))
      (node (ref "R18") (pin "P$2") (pinfunction "2_P$2") (pintype "passive"))
      (node (ref "R22") (pin "P$1") (pinfunction "1_P$1") (pintype "passive"))
      (node (ref "R26") (pin "P$1") (pinfunction "1_P$1") (pintype "passive"))
      (node (ref "TP5") (pin "P$1") (pinfunction "1_P$1") (pintype "bidirectional"))
      (node (ref "U2") (pin "7") (pinfunction "+IN_7") (pintype "input"))
    )
    (net (code "81") (name "unconnected-(IC3-PB2{slash}BOOT1-Pad20)") (class "Default")
      (node (ref "IC3") (pin "20") (pinfunction "PB2/BOOT1_20") (pintype "bidirectional"))
    )
    (net (code "82") (name "unconnected-(IC3-PB12-SPI2NSS{slash}I2C2SMBAI{slash}USART3CK{slash}TIM1BKIN-Pad25)") (class "Default")
      (node (ref "IC3") (pin "25") (pinfunction "PB12-SPI2NSS/I2C2SMBAI/USART3CK/TIM1BKIN_25") (pintype "bidirectional"))
    )
    (net (code "83") (name "unconnected-(IC3-PC13-TAMPER-RTC-Pad2)") (class "Default")
      (node (ref "IC3") (pin "2") (pinfunction "PC13-TAMPER-RTC_2") (pintype "bidirectional"))
    )
    (net (code "84") (name "unconnected-(IC3-PC14-OSC32_IN-Pad3)") (class "Default")
      (node (ref "IC3") (pin "3") (pinfunction "PC14-OSC32_IN_3") (pintype "bidirectional"))
    )
    (net (code "85") (name "unconnected-(IC3-PC15-OSC32_OUT-Pad4)") (class "Default")
      (node (ref "IC3") (pin "4") (pinfunction "PC15-OSC32_OUT_4") (pintype "bidirectional"))
    )
    (net (code "86") (name "unconnected-(IC3-PD1-OSC_OUT-CANTX-Pad6)") (class "Default")
      (node (ref "IC3") (pin "6") (pinfunction "PD1-OSC_OUT-CANTX_6") (pintype "output"))
    )
    (net (code "87") (name "unconnected-(IC5-VREF-Pad5)") (class "Default")
      (node (ref "IC5") (pin "5") (pinfunction "VREF_5") (pintype "bidirectional"))
    )
    (net (code "88") (name "unconnected-(Q1-TRI-Pad1)") (class "Default")
      (node (ref "Q1") (pin "1") (pinfunction "TRI_1") (pintype "output"))
    )
    (net (code "89") (name "unconnected-(U2A-OUT-Pad2)") (class "Default")
      (node (ref "U2") (pin "2") (pinfunction "OUT_2") (pintype "output"))
    )
  )
)
